# Serial_ID_EEPROM.net
KiCad netlist of a schematic drawn in Altium Designer
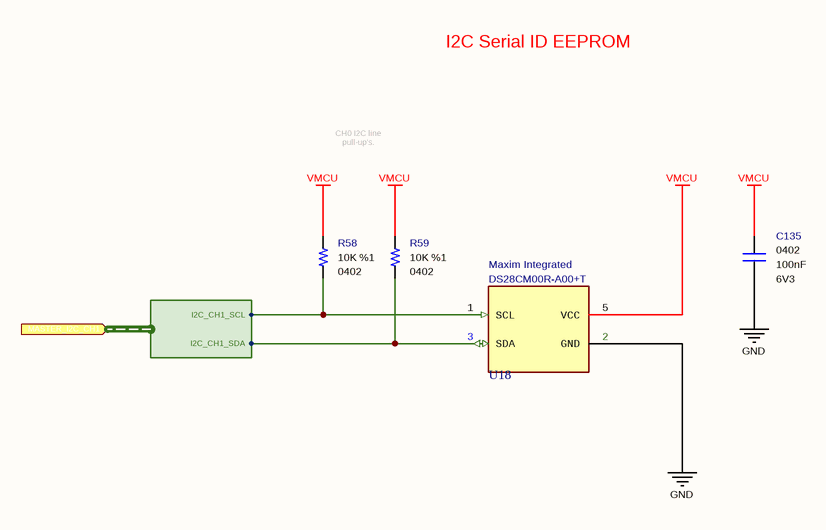
[diagram p0: Serial ID EEPROM.SchDoc]

(export (version "E")
  (design (tool "Eeschema 10.0.6"))
  (components
    (comp (ref "C135")
      (value "100nF")
      (footprint "CAPACITOR_0402")
      (description "Capacitor - 100nF [0402-6V3] (Ceramic)")
      (fields
        (field (name "TOLERANCE") "%10")
        (field (name "CASE") "0402")
        (field (name "VOLTAGE") "6V3")
        (field (name "MANUFACTURER PART NUMBER") "04026D104KAT4A")
      )
      (libsource (lib "Ovoo_Library") (part "Capacitor - 100nF [0402-6V3]"))
    )
    (comp (ref "R58")
      (value "10K")
      (footprint "RESISTOR_0402")
      (description "Thick Film Resistors - SMD 1/16 W 10 Kohms 1%")
      (fields
        (field (name "TOLERANCE") "%1")
        (field (name "CASE") "0402")
        (field (name "MANUFACTURER PART NUMBER") "CRCW040210K0FKED")
        (field (name "MOUSER PART NUMBER") "71-CRCW0402-10K-E3")
      )
      (libsource (lib "Ovoo_Library") (part "Resistor - 10K"))
    )
    (comp (ref "R59")
      (value "10K")
      (footprint "RESISTOR_0402")
      (description "Thick Film Resistors - SMD 1/16 W 10 Kohms 1%")
      (fields
        (field (name "TOLERANCE") "%1")
        (field (name "CASE") "0402")
        (field (name "MANUFACTURER PART NUMBER") "CRCW040210K0FKED")
        (field (name "MOUSER PART NUMBER") "71-CRCW0402-10K-E3")
      )
      (libsource (lib "Ovoo_Library") (part "Resistor - 10K"))
    )
    (comp (ref "U18")
      (value "Security ICs / Authentication ICs")
      (footprint "SOT-23-5")
      (description "Security ICs / Authentication ICs I C/SMBus Silicon Serial Number")
      (fields
        (field (name "MOUSER PART NUMBER") "700-DS28CM00R-A00T")
        (field (name "MANUFACTURER PART NUMBER") "DS28CM00R-A00+T")
        (field (name "MANUFACTURER NAME") "Maxim Integrated")
      )
      (libsource (lib "Ovoo_Library") (part "IC - DS28CM00R-A00+T"))
    )
  )
  (nets
    (net (code "3") (name "GND") (class "Default")
      (node (ref "C135") (pin "1") (pinfunction "1_1") (pintype "passive"))
      (node (ref "U18") (pin "2") (pinfunction "GND_2") (pintype "passive"))
    )
    (net (code "4") (name "Net-(U18-SCL)") (class "Default")
      (node (ref "R58") (pin "1") (pinfunction "1_1") (pintype "passive"))
      (node (ref "U18") (pin "1") (pinfunction "SCL_1") (pintype "input"))
    )
    (net (code "5") (name "Net-(U18-SDA)") (class "Default")
      (node (ref "R59") (pin "1") (pinfunction "1_1") (pintype "passive"))
      (node (ref "U18") (pin "3") (pinfunction "SDA_3") (pintype "bidirectional"))
    )
    (net (code "6") (name "VMCU") (class "Default")
      (node (ref "C135") (pin "2") (pinfunction "2_2") (pintype "passive"))
      (node (ref "R58") (pin "2") (pinfunction "2_2") (pintype "passive"))
      (node (ref "R59") (pin "2") (pinfunction "2_2") (pintype "passive"))
      (node (ref "U18") (pin "5") (pinfunction "VCC_5") (pintype "power_in"))
    )
    (net (code "7") (name "unconnected-(U18-NC-Pad4)") (class "Default")
      (node (ref "U18") (pin "4") (pinfunction "NC_4") (pintype "passive"))
    )
  )
)
